# Sheet1.net
KiCad netlist of a schematic drawn in Altium Designer
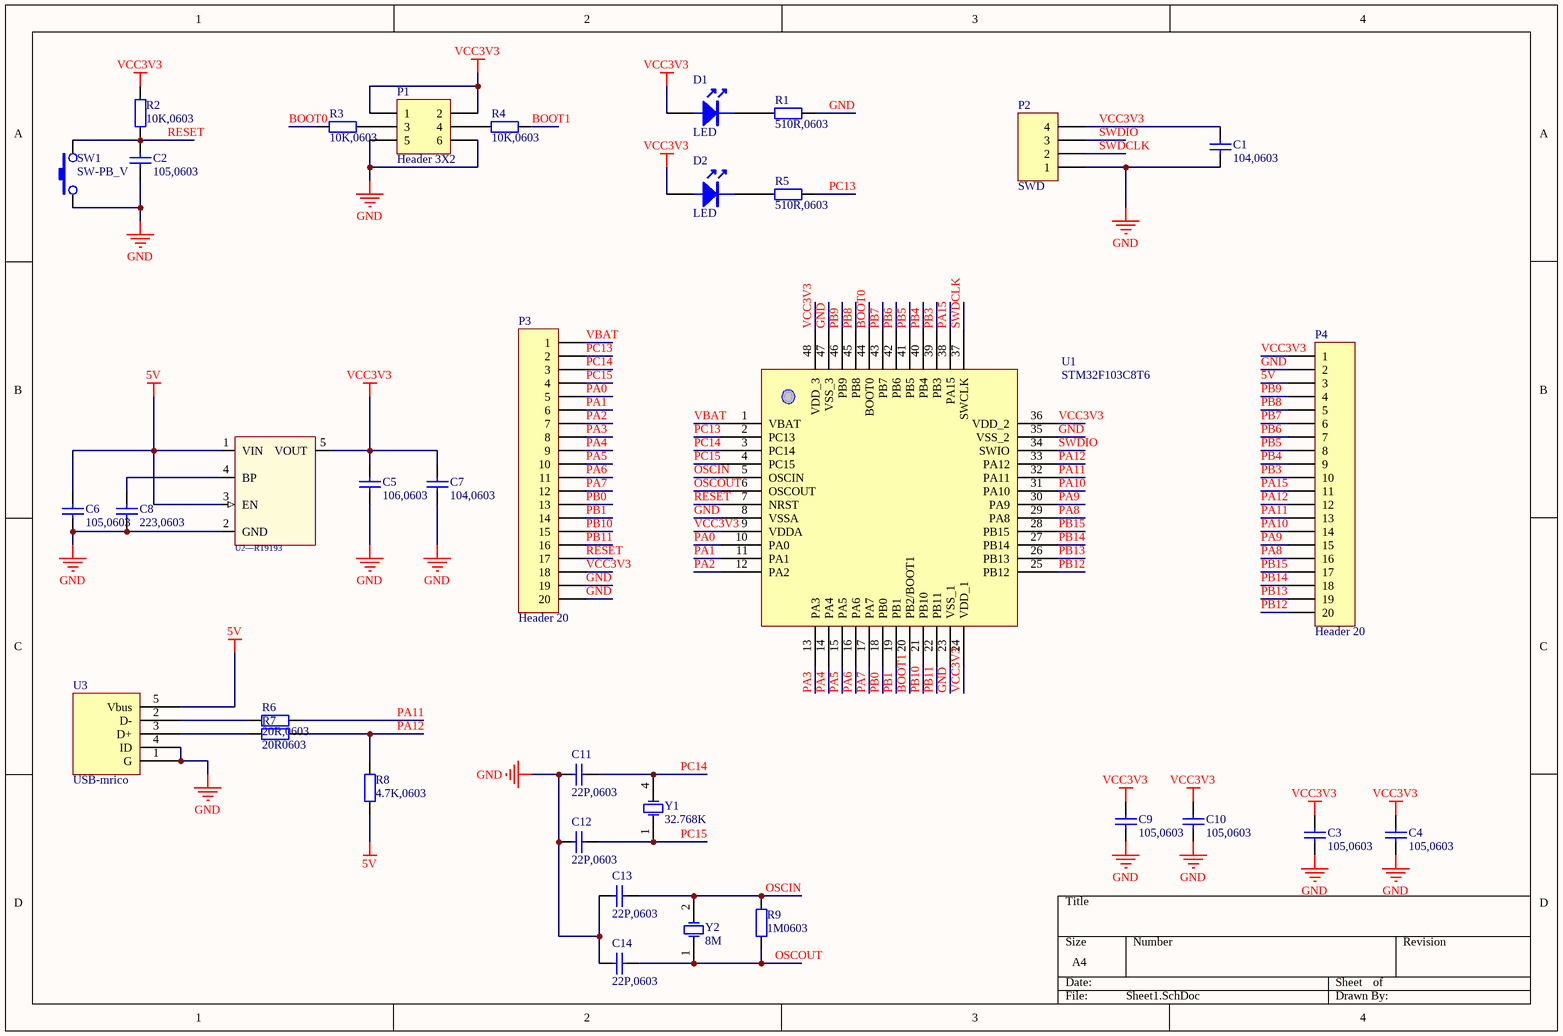
[diagram p0: Sheet1.SchDoc]

(export (version "E")
  (design (tool "Eeschema 10.0.6"))
  (components
    (comp (ref "C1")
      (value "104,0603")
      (footprint "C 0603")
      (description "Capacitor")
      (fields (field (name "PUBLISHER") "Altium Limited"))
      (libsource (lib "STM32F103C8T6") (part "Cap"))
    )
    (comp (ref "C2")
      (value "105,0603")
      (footprint "C 0603")
      (description "Capacitor")
      (fields (field (name "PUBLISHER") "Altium Limited"))
      (libsource (lib "STM32F103C8T6") (part "Cap"))
    )
    (comp (ref "C3")
      (value "105,0603")
      (footprint "C 0603")
      (description "Capacitor")
      (fields (field (name "PUBLISHER") "Altium Limited"))
      (libsource (lib "STM32F103C8T6") (part "Cap"))
    )
    (comp (ref "C4")
      (value "105,0603")
      (footprint "C 0603")
      (description "Capacitor")
      (fields (field (name "PUBLISHER") "Altium Limited"))
      (libsource (lib "STM32F103C8T6") (part "Cap"))
    )
    (comp (ref "C5")
      (value "106,0603")
      (footprint "C 0603")
      (description "Capacitor")
      (fields (field (name "PUBLISHER") "Altium Limited"))
      (libsource (lib "STM32F103C8T6") (part "Cap"))
    )
    (comp (ref "C6")
      (value "105,0603")
      (footprint "C 0603")
      (description "Capacitor")
      (fields (field (name "PUBLISHER") "Altium Limited"))
      (libsource (lib "STM32F103C8T6") (part "Cap"))
    )
    (comp (ref "C7")
      (value "104,0603")
      (footprint "C 0603")
      (description "Capacitor")
      (fields (field (name "PUBLISHER") "Altium Limited"))
      (libsource (lib "STM32F103C8T6") (part "Cap"))
    )
    (comp (ref "C8")
      (value "223,0603")
      (footprint "C 0603")
      (description "Capacitor")
      (fields (field (name "PUBLISHER") "Altium Limited"))
      (libsource (lib "STM32F103C8T6") (part "Cap"))
    )
    (comp (ref "C9")
      (value "105,0603")
      (footprint "C 0603")
      (description "Capacitor")
      (fields (field (name "PUBLISHER") "Altium Limited"))
      (libsource (lib "STM32F103C8T6") (part "Cap"))
    )
    (comp (ref "C10")
      (value "105,0603")
      (footprint "C 0603")
      (description "Capacitor")
      (fields (field (name "PUBLISHER") "Altium Limited"))
      (libsource (lib "STM32F103C8T6") (part "Cap"))
    )
    (comp (ref "C11")
      (value "22P,0603")
      (footprint "C 0603")
      (description "Capacitor")
      (fields (field (name "PUBLISHER") "Altium Limited"))
      (libsource (lib "STM32F103C8T6") (part "Cap"))
    )
    (comp (ref "C12")
      (value "22P,0603")
      (footprint "C 0603")
      (description "Capacitor")
      (fields (field (name "PUBLISHER") "Altium Limited"))
      (libsource (lib "STM32F103C8T6") (part "Cap"))
    )
    (comp (ref "C13")
      (value "22P,0603")
      (footprint "C 0603")
      (description "Capacitor")
      (fields (field (name "PUBLISHER") "Altium Limited"))
      (libsource (lib "STM32F103C8T6") (part "Cap"))
    )
    (comp (ref "C14")
      (value "22P,0603")
      (footprint "C 0603")
      (description "Capacitor")
      (fields (field (name "PUBLISHER") "Altium Limited"))
      (libsource (lib "STM32F103C8T6") (part "Cap"))
    )
    (comp (ref "D1") (value "LED") (footprint "LED 0805G") (libsource (lib "STM32F103C8T6") (part "LED")))
    (comp (ref "D2") (value "LED") (footprint "LED 0805G") (libsource (lib "STM32F103C8T6") (part "LED")))
    (comp (ref "P1")
      (value "Header 3X2")
      (footprint "HDR-3X2")
      (description "Header, 3-Pin, Dual row")
      (fields (field (name "PUBLISHER") "Altium Limited"))
      (libsource (lib "STM32F103C8T6") (part "Header 3X2"))
    )
    (comp (ref "P2")
      (value "SWD")
      (footprint "HDR-1X4_H")
      (description "Header, 4-Pin")
      (fields (field (name "PUBLISHER") "Altium Limited"))
      (libsource (lib "STM32F103C8T6") (part "Header 4"))
    )
    (comp (ref "P3")
      (value "Header 20")
      (footprint "HDR1X20")
      (description "Header, 20-Pin")
      (fields (field (name "PUBLISHER") "Altium Limited"))
      (libsource (lib "STM32F103C8T6") (part "Header 20"))
    )
    (comp (ref "P4")
      (value "Header 20")
      (footprint "HDR1X20")
      (description "Header, 20-Pin")
      (fields (field (name "PUBLISHER") "Altium Limited"))
      (libsource (lib "") (part "Header 20_1"))
    )
    (comp (ref "R1")
      (value "510R,0603")
      (footprint "R 0603")
      (description "Resistor")
      (fields (field (name "PUBLISHER") "Altium Limited"))
      (libsource (lib "STM32F103C8T6") (part "Res2"))
    )
    (comp (ref "R2")
      (value "10K,0603")
      (footprint "R 0603")
      (description "Resistor")
      (fields (field (name "PUBLISHER") "Altium Limited"))
      (libsource (lib "") (part "Res2_1"))
    )
    (comp (ref "R3")
      (value "10K,0603")
      (footprint "R 0603")
      (description "Resistor")
      (fields (field (name "PUBLISHER") "Altium Limited"))
      (libsource (lib "STM32F103C8T6") (part "Res2"))
    )
    (comp (ref "R4")
      (value "10K,0603")
      (footprint "R 0603")
      (description "Resistor")
      (fields (field (name "PUBLISHER") "Altium Limited"))
      (libsource (lib "STM32F103C8T6") (part "Res2"))
    )
    (comp (ref "R5")
      (value "510R,0603")
      (footprint "R 0603")
      (description "Resistor")
      (fields (field (name "PUBLISHER") "Altium Limited"))
      (libsource (lib "STM32F103C8T6") (part "Res2"))
    )
    (comp (ref "R6")
      (value "20R,0603")
      (footprint "R 0603")
      (description "Resistor")
      (fields (field (name "PUBLISHER") "Altium Limited"))
      (libsource (lib "STM32F103C8T6") (part "Res2"))
    )
    (comp (ref "R7")
      (value "20R0603")
      (footprint "R 0603")
      (description "Resistor")
      (fields (field (name "PUBLISHER") "Altium Limited"))
      (libsource (lib "STM32F103C8T6") (part "Res2"))
    )
    (comp (ref "R8")
      (value "4.7K,0603")
      (footprint "R 0603")
      (description "Resistor")
      (fields (field (name "PUBLISHER") "Altium Limited"))
      (libsource (lib "") (part "Res2_1"))
    )
    (comp (ref "R9")
      (value "1M0603")
      (footprint "R 0603")
      (description "Resistor")
      (fields (field (name "PUBLISHER") "Altium Limited"))
      (libsource (lib "") (part "Res2_1"))
    )
    (comp (ref "SW1")
      (value "SW-PB_V")
      (footprint "TSW SMD-3*6*2.5")
      (description "SWITCH")
      (libsource (lib "STM32F103C8T6") (part "SW-PB_V"))
    )
    (comp (ref "U1")
      (value "STM32F103C8T6")
      (footprint "TQFP48 7x7_L")
      (libsource (lib "STM32F103C8T6") (part "STM32F103C8T6"))
    )
    (comp (ref "U2—RT9193")
      (value "RT9193")
      (footprint "SOT23-5L")
      (fields (field (name "ICA_PARTNUM") "$$2191094$$RT9193-15CU5") (field (name "PART NUMBER") "TMP-13"))
      (libsource (lib "STM32F103C8T6") (part "RT9193X_5P"))
    )
    (comp (ref "U3")
      (value "USB-mrico")
      (footprint "USB-micro_B")
      (libsource (lib "STM32F103C8T6") (part "usb-STM"))
    )
    (comp (ref "Y1")
      (value "32.768K")
      (footprint "MC-306")
      (description "Crystal Oscillator")
      (fields (field (name "PUBLISHER") "Altium Limited"))
      (libsource (lib "STM32F103C8T6") (part "XTAL"))
    )
    (comp (ref "Y2")
      (value "8M")
      (footprint "XTAL-49S DIP")
      (description "Crystal Oscillator")
      (fields (field (name "PUBLISHER") "Altium Limited"))
      (libsource (lib "") (part "XTAL_1"))
    )
  )
  (nets
    (net (code "1") (name "/BOOT0") (class "Default")
      (node (ref "R3") (pin "1") (pinfunction "1_1") (pintype "passive"))
      (node (ref "U1") (pin "44") (pinfunction "BOOT0_44") (pintype "passive"))
    )
    (net (code "2") (name "/BOOT1") (class "Default")
      (node (ref "R4") (pin "2") (pinfunction "2_2") (pintype "passive"))
      (node (ref "U1") (pin "20") (pinfunction "PB2/BOOT1_20") (pintype "passive"))
    )
    (net (code "3") (name "/OSCIN") (class "Default")
      (node (ref "C13") (pin "1") (pinfunction "1_1") (pintype "passive"))
      (node (ref "R9") (pin "2") (pinfunction "2_2") (pintype "passive"))
      (node (ref "U1") (pin "5") (pinfunction "OSCIN_5") (pintype "passive"))
      (node (ref "Y2") (pin "2") (pinfunction "OSC2_2") (pintype "passive"))
    )
    (net (code "4") (name "/OSCOUT") (class "Default")
      (node (ref "C14") (pin "1") (pinfunction "1_1") (pintype "passive"))
      (node (ref "R9") (pin "1") (pinfunction "1_1") (pintype "passive"))
      (node (ref "U1") (pin "6") (pinfunction "OSCOUT_6") (pintype "passive"))
      (node (ref "Y2") (pin "1") (pinfunction "OSC1_1") (pintype "passive"))
    )
    (net (code "5") (name "/PA0") (class "Default")
      (node (ref "P3") (pin "5") (pinfunction "5_5") (pintype "passive"))
      (node (ref "U1") (pin "10") (pinfunction "PA0_10") (pintype "passive"))
    )
    (net (code "6") (name "/PA1") (class "Default")
      (node (ref "P3") (pin "6") (pinfunction "6_6") (pintype "passive"))
      (node (ref "U1") (pin "11") (pinfunction "PA1_11") (pintype "passive"))
    )
    (net (code "7") (name "/PA2") (class "Default")
      (node (ref "P3") (pin "7") (pinfunction "7_7") (pintype "passive"))
      (node (ref "U1") (pin "12") (pinfunction "PA2_12") (pintype "passive"))
    )
    (net (code "8") (name "/PA3") (class "Default")
      (node (ref "P3") (pin "8") (pinfunction "8_8") (pintype "passive"))
      (node (ref "U1") (pin "13") (pinfunction "PA3_13") (pintype "passive"))
    )
    (net (code "9") (name "/PA4") (class "Default")
      (node (ref "P3") (pin "9") (pinfunction "9_9") (pintype "passive"))
      (node (ref "U1") (pin "14") (pinfunction "PA4_14") (pintype "passive"))
    )
    (net (code "10") (name "/PA5") (class "Default")
      (node (ref "P3") (pin "10") (pinfunction "10_10") (pintype "passive"))
      (node (ref "U1") (pin "15") (pinfunction "PA5_15") (pintype "passive"))
    )
    (net (code "11") (name "/PA6") (class "Default")
      (node (ref "P3") (pin "11") (pinfunction "11_11") (pintype "passive"))
      (node (ref "U1") (pin "16") (pinfunction "PA6_16") (pintype "passive"))
    )
    (net (code "12") (name "/PA7") (class "Default")
      (node (ref "P3") (pin "12") (pinfunction "12_12") (pintype "passive"))
      (node (ref "U1") (pin "17") (pinfunction "PA7_17") (pintype "passive"))
    )
    (net (code "13") (name "/PA8") (class "Default")
      (node (ref "P4") (pin "16") (pinfunction "16_16") (pintype "passive"))
      (node (ref "U1") (pin "29") (pinfunction "PA8_29") (pintype "passive"))
    )
    (net (code "14") (name "/PA9") (class "Default")
      (node (ref "P4") (pin "15") (pinfunction "15_15") (pintype "passive"))
      (node (ref "U1") (pin "30") (pinfunction "PA9_30") (pintype "passive"))
    )
    (net (code "15") (name "/PA10") (class "Default")
      (node (ref "P4") (pin "14") (pinfunction "14_14") (pintype "passive"))
      (node (ref "U1") (pin "31") (pinfunction "PA10_31") (pintype "passive"))
    )
    (net (code "16") (name "/PA11") (class "Default")
      (node (ref "P4") (pin "13") (pinfunction "13_13") (pintype "passive"))
      (node (ref "R6") (pin "2") (pinfunction "2_2") (pintype "passive"))
      (node (ref "U1") (pin "32") (pinfunction "PA11_32") (pintype "passive"))
    )
    (net (code "17") (name "/PA12") (class "Default")
      (node (ref "P4") (pin "12") (pinfunction "12_12") (pintype "passive"))
      (node (ref "R7") (pin "2") (pinfunction "2_2") (pintype "passive"))
      (node (ref "R8") (pin "2") (pinfunction "2_2") (pintype "passive"))
      (node (ref "U1") (pin "33") (pinfunction "PA12_33") (pintype "passive"))
    )
    (net (code "18") (name "/PA15") (class "Default")
      (node (ref "P4") (pin "11") (pinfunction "11_11") (pintype "passive"))
      (node (ref "U1") (pin "38") (pinfunction "PA15_38") (pintype "passive"))
    )
    (net (code "19") (name "/PB0") (class "Default")
      (node (ref "P3") (pin "13") (pinfunction "13_13") (pintype "passive"))
      (node (ref "U1") (pin "18") (pinfunction "PB0_18") (pintype "passive"))
    )
    (net (code "20") (name "/PB1") (class "Default")
      (node (ref "P3") (pin "14") (pinfunction "14_14") (pintype "passive"))
      (node (ref "U1") (pin "19") (pinfunction "PB1_19") (pintype "passive"))
    )
    (net (code "21") (name "/PB3") (class "Default")
      (node (ref "P4") (pin "10") (pinfunction "10_10") (pintype "passive"))
      (node (ref "U1") (pin "39") (pinfunction "PB3_39") (pintype "passive"))
    )
    (net (code "22") (name "/PB4") (class "Default")
      (node (ref "P4") (pin "9") (pinfunction "9_9") (pintype "passive"))
      (node (ref "U1") (pin "40") (pinfunction "PB4_40") (pintype "passive"))
    )
    (net (code "23") (name "/PB5") (class "Default")
      (node (ref "P4") (pin "8") (pinfunction "8_8") (pintype "passive"))
      (node (ref "U1") (pin "41") (pinfunction "PB5_41") (pintype "passive"))
    )
    (net (code "24") (name "/PB6") (class "Default")
      (node (ref "P4") (pin "7") (pinfunction "7_7") (pintype "passive"))
      (node (ref "U1") (pin "42") (pinfunction "PB6_42") (pintype "passive"))
    )
    (net (code "25") (name "/PB7") (class "Default")
      (node (ref "P4") (pin "6") (pinfunction "6_6") (pintype "passive"))
      (node (ref "U1") (pin "43") (pinfunction "PB7_43") (pintype "passive"))
    )
    (net (code "26") (name "/PB8") (class "Default")
      (node (ref "P4") (pin "5") (pinfunction "5_5") (pintype "passive"))
      (node (ref "U1") (pin "45") (pinfunction "PB8_45") (pintype "passive"))
    )
    (net (code "27") (name "/PB9") (class "Default")
      (node (ref "P4") (pin "4") (pinfunction "4_4") (pintype "passive"))
      (node (ref "U1") (pin "46") (pinfunction "PB9_46") (pintype "passive"))
    )
    (net (code "28") (name "/PB10") (class "Default")
      (node (ref "P3") (pin "15") (pinfunction "15_15") (pintype "passive"))
      (node (ref "U1") (pin "21") (pinfunction "PB10_21") (pintype "passive"))
    )
    (net (code "29") (name "/PB11") (class "Default")
      (node (ref "P3") (pin "16") (pinfunction "16_16") (pintype "passive"))
      (node (ref "U1") (pin "22") (pinfunction "PB11_22") (pintype "passive"))
    )
    (net (code "30") (name "/PB12") (class "Default")
      (node (ref "P4") (pin "20") (pinfunction "20_20") (pintype "passive"))
      (node (ref "U1") (pin "25") (pinfunction "PB12_25") (pintype "passive"))
    )
    (net (code "31") (name "/PB13") (class "Default")
      (node (ref "P4") (pin "19") (pinfunction "19_19") (pintype "passive"))
      (node (ref "U1") (pin "26") (pinfunction "PB13_26") (pintype "passive"))
    )
    (net (code "32") (name "/PB14") (class "Default")
      (node (ref "P4") (pin "18") (pinfunction "18_18") (pintype "passive"))
      (node (ref "U1") (pin "27") (pinfunction "PB14_27") (pintype "passive"))
    )
    (net (code "33") (name "/PB15") (class "Default")
      (node (ref "P4") (pin "17") (pinfunction "17_17") (pintype "passive"))
      (node (ref "U1") (pin "28") (pinfunction "PB15_28") (pintype "passive"))
    )
    (net (code "34") (name "/PC13") (class "Default")
      (node (ref "P3") (pin "2") (pinfunction "2_2") (pintype "passive"))
      (node (ref "R5") (pin "2") (pinfunction "2_2") (pintype "passive"))
      (node (ref "U1") (pin "2") (pinfunction "PC13_2") (pintype "passive"))
    )
    (net (code "35") (name "/PC14") (class "Default")
      (node (ref "C11") (pin "1") (pinfunction "1_1") (pintype "passive"))
      (node (ref "P3") (pin "3") (pinfunction "3_3") (pintype "passive"))
      (node (ref "U1") (pin "3") (pinfunction "PC14_3") (pintype "passive"))
      (node (ref "Y1") (pin "4") (pinfunction "OSC2_4") (pintype "passive"))
    )
    (net (code "36") (name "/PC15") (class "Default")
      (node (ref "C12") (pin "1") (pinfunction "1_1") (pintype "passive"))
      (node (ref "P3") (pin "4") (pinfunction "4_4") (pintype "passive"))
      (node (ref "U1") (pin "4") (pinfunction "PC15_4") (pintype "passive"))
      (node (ref "Y1") (pin "1") (pinfunction "OSC1_1") (pintype "passive"))
    )
    (net (code "37") (name "/RESET") (class "Default")
      (node (ref "C2") (pin "2") (pinfunction "2_2") (pintype "passive"))
      (node (ref "P3") (pin "17") (pinfunction "17_17") (pintype "passive"))
      (node (ref "R2") (pin "1") (pinfunction "1_1") (pintype "passive"))
      (node (ref "SW1") (pin "2") (pinfunction "2_2") (pintype "passive"))
      (node (ref "U1") (pin "7") (pinfunction "NRST_7") (pintype "passive"))
    )
    (net (code "38") (name "/SWDCLK") (class "Default")
      (node (ref "P2") (pin "2") (pinfunction "2_2") (pintype "passive"))
      (node (ref "U1") (pin "37") (pinfunction "SWCLK_37") (pintype "passive"))
    )
    (net (code "39") (name "/SWDIO") (class "Default")
      (node (ref "P2") (pin "3") (pinfunction "3_3") (pintype "passive"))
      (node (ref "U1") (pin "34") (pinfunction "SWIO_34") (pintype "passive"))
    )
    (net (code "40") (name "/VBAT") (class "Default")
      (node (ref "P3") (pin "1") (pinfunction "1_1") (pintype "passive"))
      (node (ref "U1") (pin "1") (pinfunction "VBAT_1") (pintype "passive"))
    )
    (net (code "41") (name "5V") (class "Default")
      (node (ref "C6") (pin "2") (pinfunction "2_2") (pintype "passive"))
      (node (ref "P4") (pin "3") (pinfunction "3_3") (pintype "passive"))
      (node (ref "R8") (pin "1") (pinfunction "1_1") (pintype "passive"))
      (node (ref "U2—RT9193") (pin "1") (pinfunction "VIN_1") (pintype "power_in"))
      (node (ref "U2—RT9193") (pin "3") (pinfunction "EN_3") (pintype "input"))
      (node (ref "U3") (pin "5") (pinfunction "Vbus_5") (pintype "passive"))
    )
    (net (code "42") (name "GND") (class "Default")
      (node (ref "C1") (pin "1") (pinfunction "1_1") (pintype "passive"))
      (node (ref "C10") (pin "1") (pinfunction "1_1") (pintype "passive"))
      (node (ref "C11") (pin "2") (pinfunction "2_2") (pintype "passive"))
      (node (ref "C12") (pin "2") (pinfunction "2_2") (pintype "passive"))
      (node (ref "C13") (pin "2") (pinfunction "2_2") (pintype "passive"))
      (node (ref "C14") (pin "2") (pinfunction "2_2") (pintype "passive"))
      (node (ref "C2") (pin "1") (pinfunction "1_1") (pintype "passive"))
      (node (ref "C3") (pin "1") (pinfunction "1_1") (pintype "passive"))
      (node (ref "C4") (pin "1") (pinfunction "1_1") (pintype "passive"))
      (node (ref "C5") (pin "2") (pinfunction "2_2") (pintype "passive"))
      (node (ref "C6") (pin "1") (pinfunction "1_1") (pintype "passive"))
      (node (ref "C7") (pin "1") (pinfunction "1_1") (pintype "passive"))
      (node (ref "C8") (pin "1") (pinfunction "1_1") (pintype "passive"))
      (node (ref "C9") (pin "1") (pinfunction "1_1") (pintype "passive"))
      (node (ref "P1") (pin "5") (pinfunction "5_5") (pintype "passive"))
      (node (ref "P1") (pin "6") (pinfunction "6_6") (pintype "passive"))
      (node (ref "P2") (pin "1") (pinfunction "1_1") (pintype "passive"))
      (node (ref "P3") (pin "19") (pinfunction "19_19") (pintype "passive"))
      (node (ref "P3") (pin "20") (pinfunction "20_20") (pintype "passive"))
      (node (ref "P4") (pin "2") (pinfunction "2_2") (pintype "passive"))
      (node (ref "R1") (pin "2") (pinfunction "2_2") (pintype "passive"))
      (node (ref "SW1") (pin "1") (pinfunction "1_1") (pintype "passive"))
      (node (ref "U1") (pin "23") (pinfunction "VSS_1_23") (pintype "passive"))
      (node (ref "U1") (pin "35") (pinfunction "VSS_2_35") (pintype "passive"))
      (node (ref "U1") (pin "47") (pinfunction "VSS_3_47") (pintype "passive"))
      (node (ref "U1") (pin "8") (pinfunction "VSSA_8") (pintype "passive"))
      (node (ref "U2—RT9193") (pin "2") (pinfunction "GND_2") (pintype "power_in"))
      (node (ref "U3") (pin "1") (pinfunction "G_1") (pintype "passive"))
      (node (ref "U3") (pin "4") (pinfunction "ID_4") (pintype "passive"))
    )
    (net (code "43") (name "Net-(D1-Pad2)") (class "Default")
      (node (ref "D1") (pin "2") (pinfunction "2_2") (pintype "passive"))
      (node (ref "R1") (pin "1") (pinfunction "1_1") (pintype "passive"))
    )
    (net (code "44") (name "Net-(D2-Pad2)") (class "Default")
      (node (ref "D2") (pin "2") (pinfunction "2_2") (pintype "passive"))
      (node (ref "R5") (pin "1") (pinfunction "1_1") (pintype "passive"))
    )
    (net (code "45") (name "Net-(P1-Pad3)") (class "Default")
      (node (ref "P1") (pin "3") (pinfunction "3_3") (pintype "passive"))
      (node (ref "R3") (pin "2") (pinfunction "2_2") (pintype "passive"))
    )
    (net (code "46") (name "Net-(P1-Pad4)") (class "Default")
      (node (ref "P1") (pin "4") (pinfunction "4_4") (pintype "passive"))
      (node (ref "R4") (pin "1") (pinfunction "1_1") (pintype "passive"))
    )
    (net (code "47") (name "Net-(U2—RT9193-BP)") (class "Default")
      (node (ref "C8") (pin "2") (pinfunction "2_2") (pintype "passive"))
      (node (ref "U2—RT9193") (pin "4") (pinfunction "BP_4") (pintype "passive"))
    )
    (net (code "48") (name "Net-(U3-D+)") (class "Default")
      (node (ref "R7") (pin "1") (pinfunction "1_1") (pintype "passive"))
      (node (ref "U3") (pin "3") (pinfunction "D+_3") (pintype "passive"))
    )
    (net (code "49") (name "Net-(U3-D-)") (class "Default")
      (node (ref "R6") (pin "1") (pinfunction "1_1") (pintype "passive"))
      (node (ref "U3") (pin "2") (pinfunction "D-_2") (pintype "passive"))
    )
    (net (code "50") (name "VCC3V3") (class "Default")
      (node (ref "C1") (pin "2") (pinfunction "2_2") (pintype "passive"))
      (node (ref "C10") (pin "2") (pinfunction "2_2") (pintype "passive"))
      (node (ref "C3") (pin "2") (pinfunction "2_2") (pintype "passive"))
      (node (ref "C4") (pin "2") (pinfunction "2_2") (pintype "passive"))
      (node (ref "C5") (pin "1") (pinfunction "1_1") (pintype "passive"))
      (node (ref "C7") (pin "2") (pinfunction "2_2") (pintype "passive"))
      (node (ref "C9") (pin "2") (pinfunction "2_2") (pintype "passive"))
      (node (ref "D1") (pin "1") (pinfunction "1_1") (pintype "passive"))
      (node (ref "D2") (pin "1") (pinfunction "1_1") (pintype "passive"))
      (node (ref "P1") (pin "1") (pinfunction "1_1") (pintype "passive"))
      (node (ref "P1") (pin "2") (pinfunction "2_2") (pintype "passive"))
      (node (ref "P2") (pin "4") (pinfunction "4_4") (pintype "passive"))
      (node (ref "P3") (pin "18") (pinfunction "18_18") (pintype "passive"))
      (node (ref "P4") (pin "1") (pinfunction "1_1") (pintype "passive"))
      (node (ref "R2") (pin "2") (pinfunction "2_2") (pintype "passive"))
      (node (ref "U1") (pin "24") (pinfunction "VDD_1_24") (pintype "passive"))
      (node (ref "U1") (pin "36") (pinfunction "VDD_2_36") (pintype "passive"))
      (node (ref "U1") (pin "48") (pinfunction "VDD_3_48") (pintype "passive"))
      (node (ref "U1") (pin "9") (pinfunction "VDDA_9") (pintype "passive"))
      (node (ref "U2—RT9193") (pin "5") (pinfunction "VOUT_5") (pintype "power_in"))
    )
  )
)
